# Compensador.net
KiCad netlist of a schematic drawn in Altium Designer
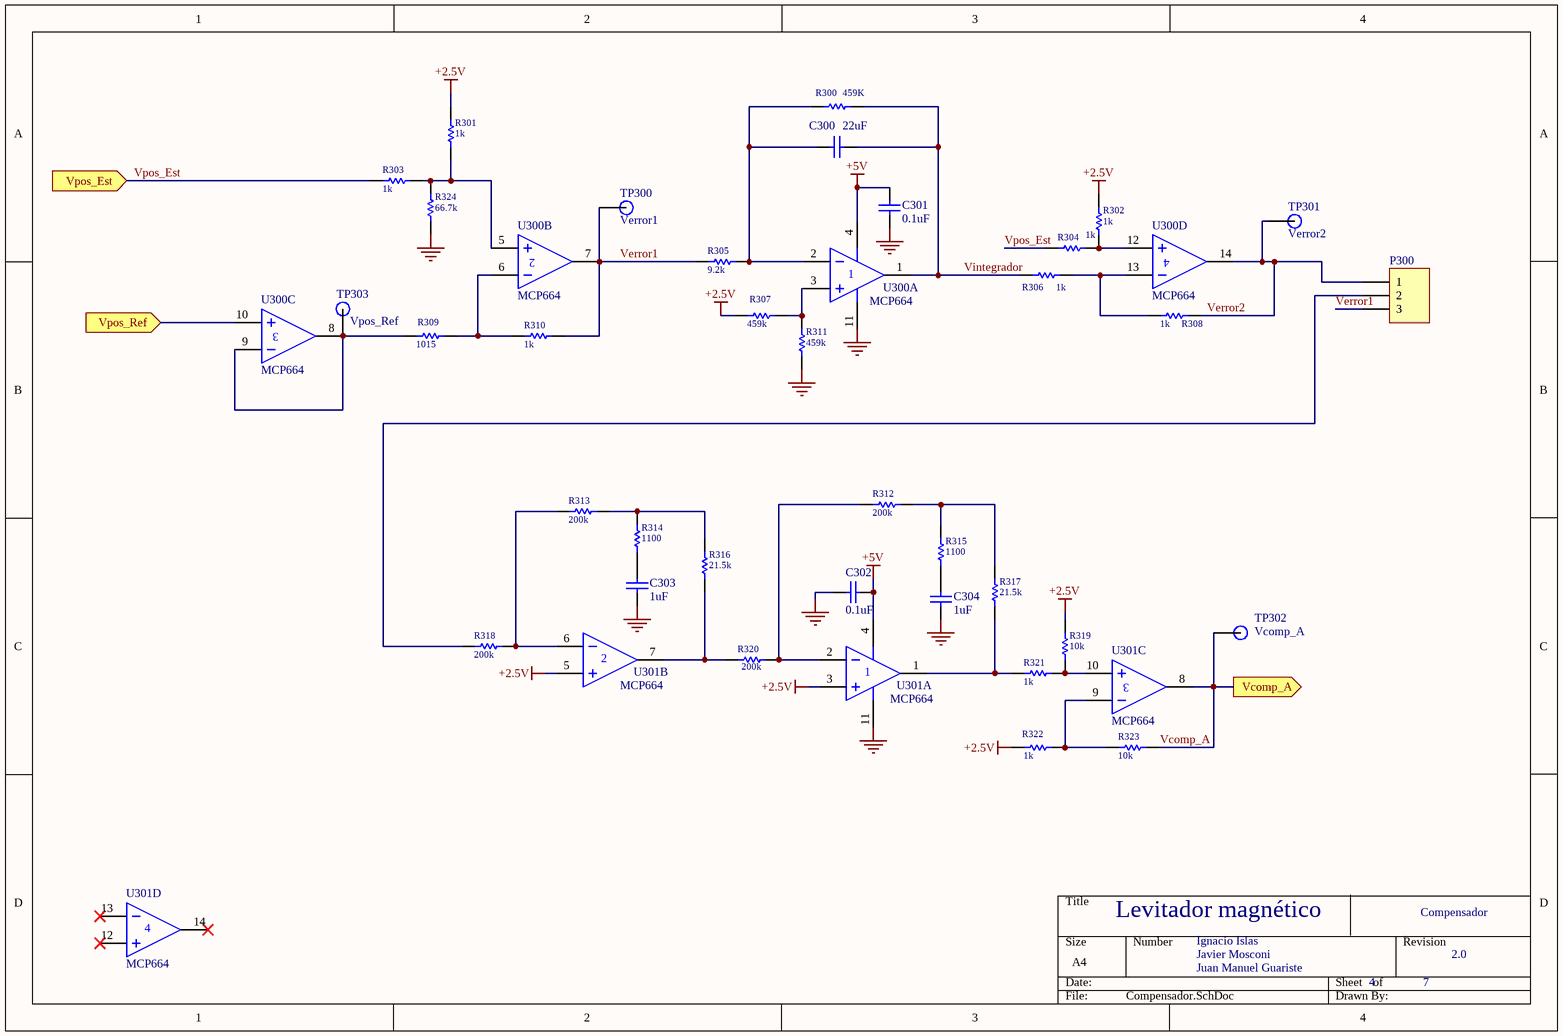
[diagram p0: Compensador.SchDoc]

(export (version "E")
  (design (tool "Eeschema 10.0.6"))
  (components
    (comp (ref "C300")
      (value "22uF")
      (footprint "C1206")
      (description "CAP CER 22UF 16V X5R 1206")
      (fields (field (name "MANUFACTURER") "Samsung Electro-Mechanics") (field (name "Comment") "Capacitor"))
      (libsource (lib "Levitador_GMI") (part "Capacitor"))
    )
    (comp (ref "C301")
      (value "0.1uF")
      (footprint "C1206")
      (description "CAP CER 0.1UF 50V X7R 1206")
      (fields (field (name "MANUFACTURER") "Venkel") (field (name "Comment") "Capacitor"))
      (libsource (lib "Levitador_GMI") (part "Capacitor"))
    )
    (comp (ref "C302")
      (value "0.1uF")
      (footprint "C1206")
      (description "CAP CER 0.1UF 50V X7R 1206")
      (fields (field (name "MANUFACTURER") "Venkel") (field (name "Comment") "Capacitor"))
      (libsource (lib "Levitador_GMI") (part "Capacitor"))
    )
    (comp (ref "C303")
      (value "1uF")
      (footprint "C1206")
      (description "CAP CER 1UF 25V X7R 1206")
      (fields (field (name "MANUFACTURER") "CAL-CHIP ELECTRONICS, INC.") (field (name "Comment") "Capacitor"))
      (libsource (lib "Levitador_GMI") (part "Capacitor"))
    )
    (comp (ref "C304")
      (value "1uF")
      (footprint "C1206")
      (description "CAP CER 1UF 25V X7R 1206")
      (fields (field (name "MANUFACTURER") "CAL-CHIP ELECTRONICS, INC.") (field (name "Comment") "Capacitor"))
      (libsource (lib "Levitador_GMI") (part "Capacitor"))
    )
    (comp (ref "P300")
      (value "Header 3")
      (footprint "HDR1X3")
      (description "TERM BLK 3P SIDE ENT 2.54MM PCB")
      (fields (field (name "MANUFACTURER") "TE Connectivity AMP Connectors"))
      (libsource (lib "Levitador_GMI") (part "Header 3"))
    )
    (comp (ref "R300")
      (value "459K")
      (footprint "Levitador_GMI:R1206")
      (description "RES 459K OHM 1% 1/4W 1206")
      (fields (field (name "MANUFACTURER") "KOA Speer Electronics, Inc.") (field (name "TOLERANCE") "1%"))
      (libsource (lib "Levitador_GMI") (part "R1206"))
    )
    (comp (ref "R301")
      (value "1k")
      (footprint "Levitador_GMI:R1206")
      (description "RES 1K OHM 1% 1/4W 1206")
      (fields (field (name "MANUFACTURER") "Stackpole Electronics Inc") (field (name "TOLERANCE") "1%"))
      (libsource (lib "Levitador_GMI") (part "R1206"))
    )
    (comp (ref "R302")
      (value "1k")
      (footprint "Levitador_GMI:R1206")
      (description "RES 1K OHM 1% 1/4W 1206")
      (fields (field (name "MANUFACTURER") "Stackpole Electronics Inc") (field (name "TOLERANCE") "1%"))
      (libsource (lib "Levitador_GMI") (part "R1206"))
    )
    (comp (ref "R303")
      (value "1k")
      (footprint "Levitador_GMI:R1206")
      (description "RES 1K OHM 1% 1/4W 1206")
      (fields (field (name "MANUFACTURER") "Stackpole Electronics Inc") (field (name "TOLERANCE") "1%"))
      (libsource (lib "Levitador_GMI") (part "R1206"))
    )
    (comp (ref "R304")
      (value "1k")
      (footprint "Levitador_GMI:R1206")
      (description "RES 1K OHM 1% 1/4W 1206")
      (fields (field (name "MANUFACTURER") "Stackpole Electronics Inc") (field (name "TOLERANCE") "1%"))
      (libsource (lib "Levitador_GMI") (part "R1206"))
    )
    (comp (ref "R305")
      (value "9.2k")
      (footprint "Levitador_GMI:R1206")
      (description "RES 9.2K OHM 1% 1/4W 1206")
      (fields (field (name "MANUFACTURER") "KOA Speer Electronics, Inc.") (field (name "TOLERANCE") "1%"))
      (libsource (lib "Levitador_GMI") (part "R1206"))
    )
    (comp (ref "R306")
      (value "1k")
      (footprint "Levitador_GMI:R1206")
      (description "RES 1K OHM 1% 1/4W 1206")
      (fields (field (name "MANUFACTURER") "Stackpole Electronics Inc") (field (name "TOLERANCE") "1%"))
      (libsource (lib "Levitador_GMI") (part "R1206"))
    )
    (comp (ref "R307")
      (value "459k")
      (footprint "Levitador_GMI:R1206")
      (description "RES 459K OHM 1% 1/4W 1206")
      (fields (field (name "MANUFACTURER") "KOA Speer Electronics, Inc.") (field (name "TOLERANCE") "1%"))
      (libsource (lib "Levitador_GMI") (part "R1206"))
    )
    (comp (ref "R308")
      (value "1k")
      (footprint "Levitador_GMI:R1206")
      (description "RES 1K OHM 1% 1/4W 1206")
      (fields (field (name "MANUFACTURER") "Stackpole Electronics Inc") (field (name "TOLERANCE") "1%"))
      (libsource (lib "Levitador_GMI") (part "R1206"))
    )
    (comp (ref "R309")
      (value "1015")
      (footprint "Levitador_GMI:R1206")
      (description "RES 1.01K OHM 0.1% 1/3W 1206")
      (fields (field (name "MANUFACTURER") "Stackpole Electronics Inc") (field (name "TOLERANCE") "1%"))
      (libsource (lib "Levitador_GMI") (part "R1206"))
    )
    (comp (ref "R310")
      (value "1k")
      (footprint "Levitador_GMI:R1206")
      (description "RES 1K OHM 1% 1/4W 1206")
      (fields (field (name "MANUFACTURER") "Stackpole Electronics Inc") (field (name "TOLERANCE") "1%"))
      (libsource (lib "Levitador_GMI") (part "R1206"))
    )
    (comp (ref "R311")
      (value "459k")
      (footprint "Levitador_GMI:R1206")
      (description "RES 9.2K OHM 1% 1/4W 1206")
      (fields (field (name "MANUFACTURER") "KOA Speer Electronics, Inc.") (field (name "TOLERANCE") "1%"))
      (libsource (lib "Levitador_GMI") (part "R1206"))
    )
    (comp (ref "R312")
      (value "200k")
      (footprint "Levitador_GMI:R1206")
      (description "RES 200K OHM 1% 1/4W 1206")
      (fields (field (name "MANUFACTURER") "YAGEO") (field (name "TOLERANCE") "1%"))
      (libsource (lib "Levitador_GMI") (part "R1206"))
    )
    (comp (ref "R313")
      (value "200k")
      (footprint "Levitador_GMI:R1206")
      (description "RES 200K OHM 1% 1/4W 1206")
      (fields (field (name "MANUFACTURER") "YAGEO") (field (name "TOLERANCE") "1%"))
      (libsource (lib "Levitador_GMI") (part "R1206"))
    )
    (comp (ref "R314")
      (value "1100")
      (footprint "Levitador_GMI:R1206")
      (description "RES 1.1K OHM 1% 1/4W 1206")
      (fields (field (name "MANUFACTURER") "YAGEO") (field (name "TOLERANCE") "1%"))
      (libsource (lib "Levitador_GMI") (part "R1206"))
    )
    (comp (ref "R315")
      (value "1100")
      (footprint "Levitador_GMI:R1206")
      (description "RES 1.1K OHM 1% 1/4W 1206")
      (fields (field (name "MANUFACTURER") "YAGEO") (field (name "TOLERANCE") "1%"))
      (libsource (lib "Levitador_GMI") (part "R1206"))
    )
    (comp (ref "R316")
      (value "21.5k")
      (footprint "Levitador_GMI:R1206")
      (description "RES 21.5K OHM 1% 1/4W 1206")
      (fields (field (name "MANUFACTURER") "YAGEO") (field (name "TOLERANCE") "1%"))
      (libsource (lib "Levitador_GMI") (part "R1206"))
    )
    (comp (ref "R317")
      (value "21.5k")
      (footprint "Levitador_GMI:R1206")
      (description "RES 21.5K OHM 1% 1/4W 1206")
      (fields (field (name "MANUFACTURER") "YAGEO") (field (name "TOLERANCE") "1%"))
      (libsource (lib "Levitador_GMI") (part "R1206"))
    )
    (comp (ref "R318")
      (value "200k")
      (footprint "Levitador_GMI:R1206")
      (description "RES 200K OHM 1% 1/4W 1206")
      (fields (field (name "MANUFACTURER") "YAGEO") (field (name "TOLERANCE") "1%"))
      (libsource (lib "Levitador_GMI") (part "R1206"))
    )
    (comp (ref "R319")
      (value "10k")
      (footprint "Levitador_GMI:R1206")
      (description "RES 10K OHM 1% 1/4W 1206")
      (fields (field (name "MANUFACTURER") "YAGEO") (field (name "TOLERANCE") "1%"))
      (libsource (lib "Levitador_GMI") (part "R1206"))
    )
    (comp (ref "R320")
      (value "200k")
      (footprint "Levitador_GMI:R1206")
      (description "RES 200K OHM 1% 1/4W 1206")
      (fields (field (name "MANUFACTURER") "YAGEO") (field (name "TOLERANCE") "1%"))
      (libsource (lib "Levitador_GMI") (part "R1206"))
    )
    (comp (ref "R321")
      (value "1k")
      (footprint "Levitador_GMI:R1206")
      (description "RES 1K OHM 1% 1/4W 1206")
      (fields (field (name "MANUFACTURER") "Stackpole Electronics Inc") (field (name "TOLERANCE") "1%"))
      (libsource (lib "Levitador_GMI") (part "R1206"))
    )
    (comp (ref "R322")
      (value "1k")
      (footprint "Levitador_GMI:R1206")
      (description "RES 1K OHM 1% 1/4W 1206")
      (fields (field (name "MANUFACTURER") "Stackpole Electronics Inc") (field (name "TOLERANCE") "1%"))
      (libsource (lib "Levitador_GMI") (part "R1206"))
    )
    (comp (ref "R323")
      (value "10k")
      (footprint "Levitador_GMI:R1206")
      (description "RES 10K OHM 1% 1/4W 1206")
      (fields (field (name "MANUFACTURER") "YAGEO") (field (name "TOLERANCE") "1%"))
      (libsource (lib "Levitador_GMI") (part "R1206"))
    )
    (comp (ref "R324")
      (value "66.7k")
      (footprint "Levitador_GMI:R1206")
      (description "RES 1K OHM 1% 1/4W 1206")
      (fields (field (name "MANUFACTURER") "YAGEO") (field (name "TOLERANCE") "1%"))
      (libsource (lib "Levitador_GMI") (part "R1206"))
    )
    (comp (ref "TP300")
      (value "Verror1")
      (footprint "TestPoint Keystone 5000 Silver-Red")
      (description "PC TEST POINT MINIATURE RED")
      (fields (field (name "MANUFACTURER") "Keystone Electronics"))
      (libsource (lib "Levitador_GMI") (part "Testpoint"))
    )
    (comp (ref "TP301")
      (value "Verror2")
      (footprint "TestPoint Keystone 5000 Silver-Red")
      (description "PC TEST POINT MINIATURE RED")
      (fields (field (name "MANUFACTURER") "Keystone Electronics"))
      (libsource (lib "Levitador_GMI") (part "Testpoint"))
    )
    (comp (ref "TP302")
      (value "Vcomp_A")
      (footprint "TestPoint Keystone 5000 Silver-Red")
      (description "PC TEST POINT MINIATURE RED")
      (fields (field (name "MANUFACTURER") "Keystone Electronics"))
      (libsource (lib "Levitador_GMI") (part "Testpoint"))
    )
    (comp (ref "TP303")
      (value "Vpos_Ref")
      (footprint "TestPoint Keystone 5000 Silver-Red")
      (description "PC TEST POINT MINIATURE RED")
      (fields (field (name "MANUFACTURER") "Keystone Electronics"))
      (libsource (lib "Levitador_GMI") (part "Testpoint"))
    )
    (comp (ref "U300")
      (value "MCP664")
      (footprint "SOIC14")
      (description "IC OPAMP GP 4 CIRCUIT 14TSSOP")
      (fields (field (name "MANUFACTURER") "Microchip Technology"))
      (libsource (lib "Levitador_GMI") (part "MCP664"))
    )
    (comp (ref "U301")
      (value "MCP664")
      (footprint "SOIC14")
      (description "IC OPAMP GP 4 CIRCUIT 14TSSOP")
      (fields (field (name "MANUFACTURER") "Microchip Technology"))
      (libsource (lib "Levitador_GMI") (part "MCP664"))
    )
  )
  (nets
    (net (code "1") (name "+2.5V") (class "Default")
      (node (ref "R301") (pin "2") (pinfunction "2_2") (pintype "passive"))
      (node (ref "R302") (pin "2") (pinfunction "2_2") (pintype "passive"))
      (node (ref "R307") (pin "1") (pinfunction "1_1") (pintype "passive"))
      (node (ref "R319") (pin "2") (pinfunction "2_2") (pintype "passive"))
      (node (ref "R322") (pin "1") (pinfunction "1_1") (pintype "passive"))
      (node (ref "U301") (pin "3") (pinfunction "IN+_3") (pintype "passive"))
      (node (ref "U301") (pin "5") (pinfunction "IN+_5") (pintype "passive"))
    )
    (net (code "2") (name "+5V") (class "Default")
      (node (ref "C301") (pin "2") (pinfunction "2_2") (pintype "passive"))
      (node (ref "C302") (pin "2") (pinfunction "2_2") (pintype "passive"))
      (node (ref "U300") (pin "4") (pinfunction "V+_4") (pintype "power_in"))
      (node (ref "U301") (pin "4") (pinfunction "V+_4") (pintype "power_in"))
    )
    (net (code "3") (name "/Vcomp_A") (class "Default")
      (node (ref "R323") (pin "2") (pinfunction "2_2") (pintype "passive"))
      (node (ref "TP302") (pin "1") (pinfunction "1_1") (pintype "passive"))
      (node (ref "U301") (pin "8") (pinfunction "OUT_8") (pintype "passive"))
    )
    (net (code "4") (name "/Verror1") (class "Default")
      (node (ref "P300") (pin "3") (pinfunction "3_3") (pintype "passive"))
      (node (ref "R305") (pin "1") (pinfunction "1_1") (pintype "passive"))
      (node (ref "R310") (pin "2") (pinfunction "2_2") (pintype "passive"))
      (node (ref "TP300") (pin "1") (pinfunction "1_1") (pintype "passive"))
      (node (ref "U300") (pin "7") (pinfunction "OUT_7") (pintype "passive"))
    )
    (net (code "5") (name "/Verror2") (class "Default")
      (node (ref "P300") (pin "1") (pinfunction "1_1") (pintype "passive"))
      (node (ref "R308") (pin "2") (pinfunction "2_2") (pintype "passive"))
      (node (ref "TP301") (pin "1") (pinfunction "1_1") (pintype "passive"))
      (node (ref "U300") (pin "14") (pinfunction "OUT_14") (pintype "passive"))
    )
    (net (code "6") (name "/Vintegrador") (class "Default")
      (node (ref "C300") (pin "1") (pinfunction "1_1") (pintype "passive"))
      (node (ref "R300") (pin "2") (pinfunction "2_2") (pintype "passive"))
      (node (ref "R306") (pin "1") (pinfunction "1_1") (pintype "passive"))
      (node (ref "U300") (pin "1") (pinfunction "OUT_1") (pintype "passive"))
    )
    (net (code "7") (name "/Vpos_Est") (class "Default")
      (node (ref "R303") (pin "1") (pinfunction "1_1") (pintype "passive"))
      (node (ref "R304") (pin "1") (pinfunction "1_1") (pintype "passive"))
    )
    (net (code "8") (name "/Vpos_Ref") (class "Default")
      (node (ref "U300") (pin "10") (pinfunction "IN+_10") (pintype "passive"))
    )
    (net (code "9") (name "GND") (class "Default")
      (node (ref "C301") (pin "1") (pinfunction "1_1") (pintype "passive"))
      (node (ref "C302") (pin "1") (pinfunction "1_1") (pintype "passive"))
      (node (ref "C303") (pin "2") (pinfunction "2_2") (pintype "passive"))
      (node (ref "C304") (pin "1") (pinfunction "1_1") (pintype "passive"))
      (node (ref "R311") (pin "1") (pinfunction "1_1") (pintype "passive"))
      (node (ref "R324") (pin "2") (pinfunction "2_2") (pintype "passive"))
      (node (ref "U300") (pin "11") (pinfunction "V-_11") (pintype "power_in"))
      (node (ref "U301") (pin "11") (pinfunction "V-_11") (pintype "power_in"))
    )
    (net (code "10") (name "Net-(C303-Pad1)") (class "Default")
      (node (ref "C303") (pin "1") (pinfunction "1_1") (pintype "passive"))
      (node (ref "R314") (pin "1") (pinfunction "1_1") (pintype "passive"))
    )
    (net (code "11") (name "Net-(C304-Pad2)") (class "Default")
      (node (ref "C304") (pin "2") (pinfunction "2_2") (pintype "passive"))
      (node (ref "R315") (pin "1") (pinfunction "1_1") (pintype "passive"))
    )
    (net (code "12") (name "Net-(P300-Pad2)") (class "Default")
      (node (ref "P300") (pin "2") (pinfunction "2_2") (pintype "passive"))
      (node (ref "R318") (pin "1") (pinfunction "1_1") (pintype "passive"))
    )
    (net (code "13") (name "Net-(R312-Pad2)") (class "Default")
      (node (ref "R312") (pin "2") (pinfunction "2_2") (pintype "passive"))
      (node (ref "R315") (pin "2") (pinfunction "2_2") (pintype "passive"))
      (node (ref "R317") (pin "2") (pinfunction "2_2") (pintype "passive"))
    )
    (net (code "14") (name "Net-(R313-Pad2)") (class "Default")
      (node (ref "R313") (pin "2") (pinfunction "2_2") (pintype "passive"))
      (node (ref "R314") (pin "2") (pinfunction "2_2") (pintype "passive"))
      (node (ref "R316") (pin "2") (pinfunction "2_2") (pintype "passive"))
    )
    (net (code "15") (name "Net-(U300A-IN+)") (class "Default")
      (node (ref "R307") (pin "2") (pinfunction "2_2") (pintype "passive"))
      (node (ref "R311") (pin "2") (pinfunction "2_2") (pintype "passive"))
      (node (ref "U300") (pin "3") (pinfunction "IN+_3") (pintype "passive"))
    )
    (net (code "16") (name "Net-(U300A-IN-)") (class "Default")
      (node (ref "C300") (pin "2") (pinfunction "2_2") (pintype "passive"))
      (node (ref "R300") (pin "1") (pinfunction "1_1") (pintype "passive"))
      (node (ref "R305") (pin "2") (pinfunction "2_2") (pintype "passive"))
      (node (ref "U300") (pin "2") (pinfunction "IN-_2") (pintype "passive"))
    )
    (net (code "17") (name "Net-(U300B-IN+)") (class "Default")
      (node (ref "R301") (pin "1") (pinfunction "1_1") (pintype "passive"))
      (node (ref "R303") (pin "2") (pinfunction "2_2") (pintype "passive"))
      (node (ref "R324") (pin "1") (pinfunction "1_1") (pintype "passive"))
      (node (ref "U300") (pin "5") (pinfunction "IN+_5") (pintype "passive"))
    )
    (net (code "18") (name "Net-(U300B-IN-)") (class "Default")
      (node (ref "R309") (pin "2") (pinfunction "2_2") (pintype "passive"))
      (node (ref "R310") (pin "1") (pinfunction "1_1") (pintype "passive"))
      (node (ref "U300") (pin "6") (pinfunction "IN-_6") (pintype "passive"))
    )
    (net (code "19") (name "Net-(U300C-IN-)") (class "Default")
      (node (ref "R309") (pin "1") (pinfunction "1_1") (pintype "passive"))
      (node (ref "TP303") (pin "1") (pinfunction "1_1") (pintype "passive"))
      (node (ref "U300") (pin "8") (pinfunction "OUT_8") (pintype "passive"))
      (node (ref "U300") (pin "9") (pinfunction "IN-_9") (pintype "passive"))
    )
    (net (code "20") (name "Net-(U300D-IN+)") (class "Default")
      (node (ref "R302") (pin "1") (pinfunction "1_1") (pintype "passive"))
      (node (ref "R304") (pin "2") (pinfunction "2_2") (pintype "passive"))
      (node (ref "U300") (pin "12") (pinfunction "IN+_12") (pintype "passive"))
    )
    (net (code "21") (name "Net-(U300D-IN-)") (class "Default")
      (node (ref "R306") (pin "2") (pinfunction "2_2") (pintype "passive"))
      (node (ref "R308") (pin "1") (pinfunction "1_1") (pintype "passive"))
      (node (ref "U300") (pin "13") (pinfunction "IN-_13") (pintype "passive"))
    )
    (net (code "22") (name "Net-(U301A-IN-)") (class "Default")
      (node (ref "R312") (pin "1") (pinfunction "1_1") (pintype "passive"))
      (node (ref "R320") (pin "2") (pinfunction "2_2") (pintype "passive"))
      (node (ref "U301") (pin "2") (pinfunction "IN-_2") (pintype "passive"))
    )
    (net (code "23") (name "Net-(U301A-OUT)") (class "Default")
      (node (ref "R317") (pin "1") (pinfunction "1_1") (pintype "passive"))
      (node (ref "R321") (pin "1") (pinfunction "1_1") (pintype "passive"))
      (node (ref "U301") (pin "1") (pinfunction "OUT_1") (pintype "passive"))
    )
    (net (code "24") (name "Net-(U301B-IN-)") (class "Default")
      (node (ref "R313") (pin "1") (pinfunction "1_1") (pintype "passive"))
      (node (ref "R318") (pin "2") (pinfunction "2_2") (pintype "passive"))
      (node (ref "U301") (pin "6") (pinfunction "IN-_6") (pintype "passive"))
    )
    (net (code "25") (name "Net-(U301B-OUT)") (class "Default")
      (node (ref "R316") (pin "1") (pinfunction "1_1") (pintype "passive"))
      (node (ref "R320") (pin "1") (pinfunction "1_1") (pintype "passive"))
      (node (ref "U301") (pin "7") (pinfunction "OUT_7") (pintype "passive"))
    )
    (net (code "26") (name "Net-(U301C-IN+)") (class "Default")
      (node (ref "R319") (pin "1") (pinfunction "1_1") (pintype "passive"))
      (node (ref "R321") (pin "2") (pinfunction "2_2") (pintype "passive"))
      (node (ref "U301") (pin "10") (pinfunction "IN+_10") (pintype "passive"))
    )
    (net (code "27") (name "Net-(U301C-IN-)") (class "Default")
      (node (ref "R322") (pin "2") (pinfunction "2_2") (pintype "passive"))
      (node (ref "R323") (pin "1") (pinfunction "1_1") (pintype "passive"))
      (node (ref "U301") (pin "9") (pinfunction "IN-_9") (pintype "passive"))
    )
    (net (code "28") (name "unconnected-(U301D-IN+-Pad12)") (class "Default")
      (node (ref "U301") (pin "12") (pinfunction "IN+_12") (pintype "passive+no_connect"))
    )
    (net (code "29") (name "unconnected-(U301D-IN--Pad13)") (class "Default")
      (node (ref "U301") (pin "13") (pinfunction "IN-_13") (pintype "passive+no_connect"))
    )
    (net (code "30") (name "unconnected-(U301D-OUT-Pad14)") (class "Default")
      (node (ref "U301") (pin "14") (pinfunction "OUT_14") (pintype "passive+no_connect"))
    )
  )
)
